# PDU_v3_1.net
KiCad netlist of a schematic drawn in EAGLE
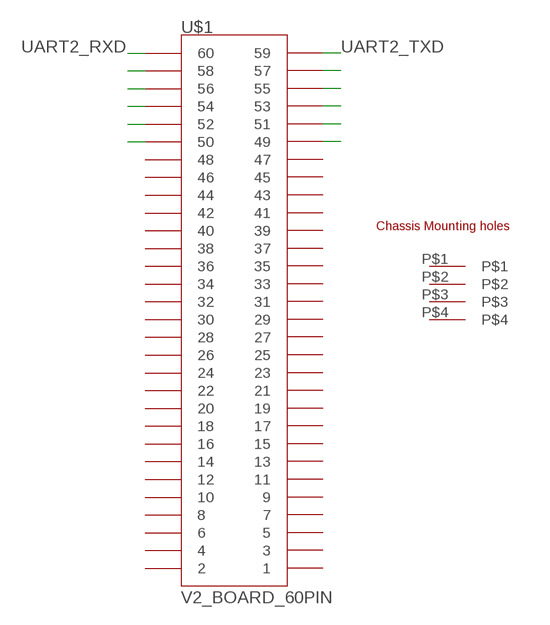
[diagram p0: schematic, sheet 1]
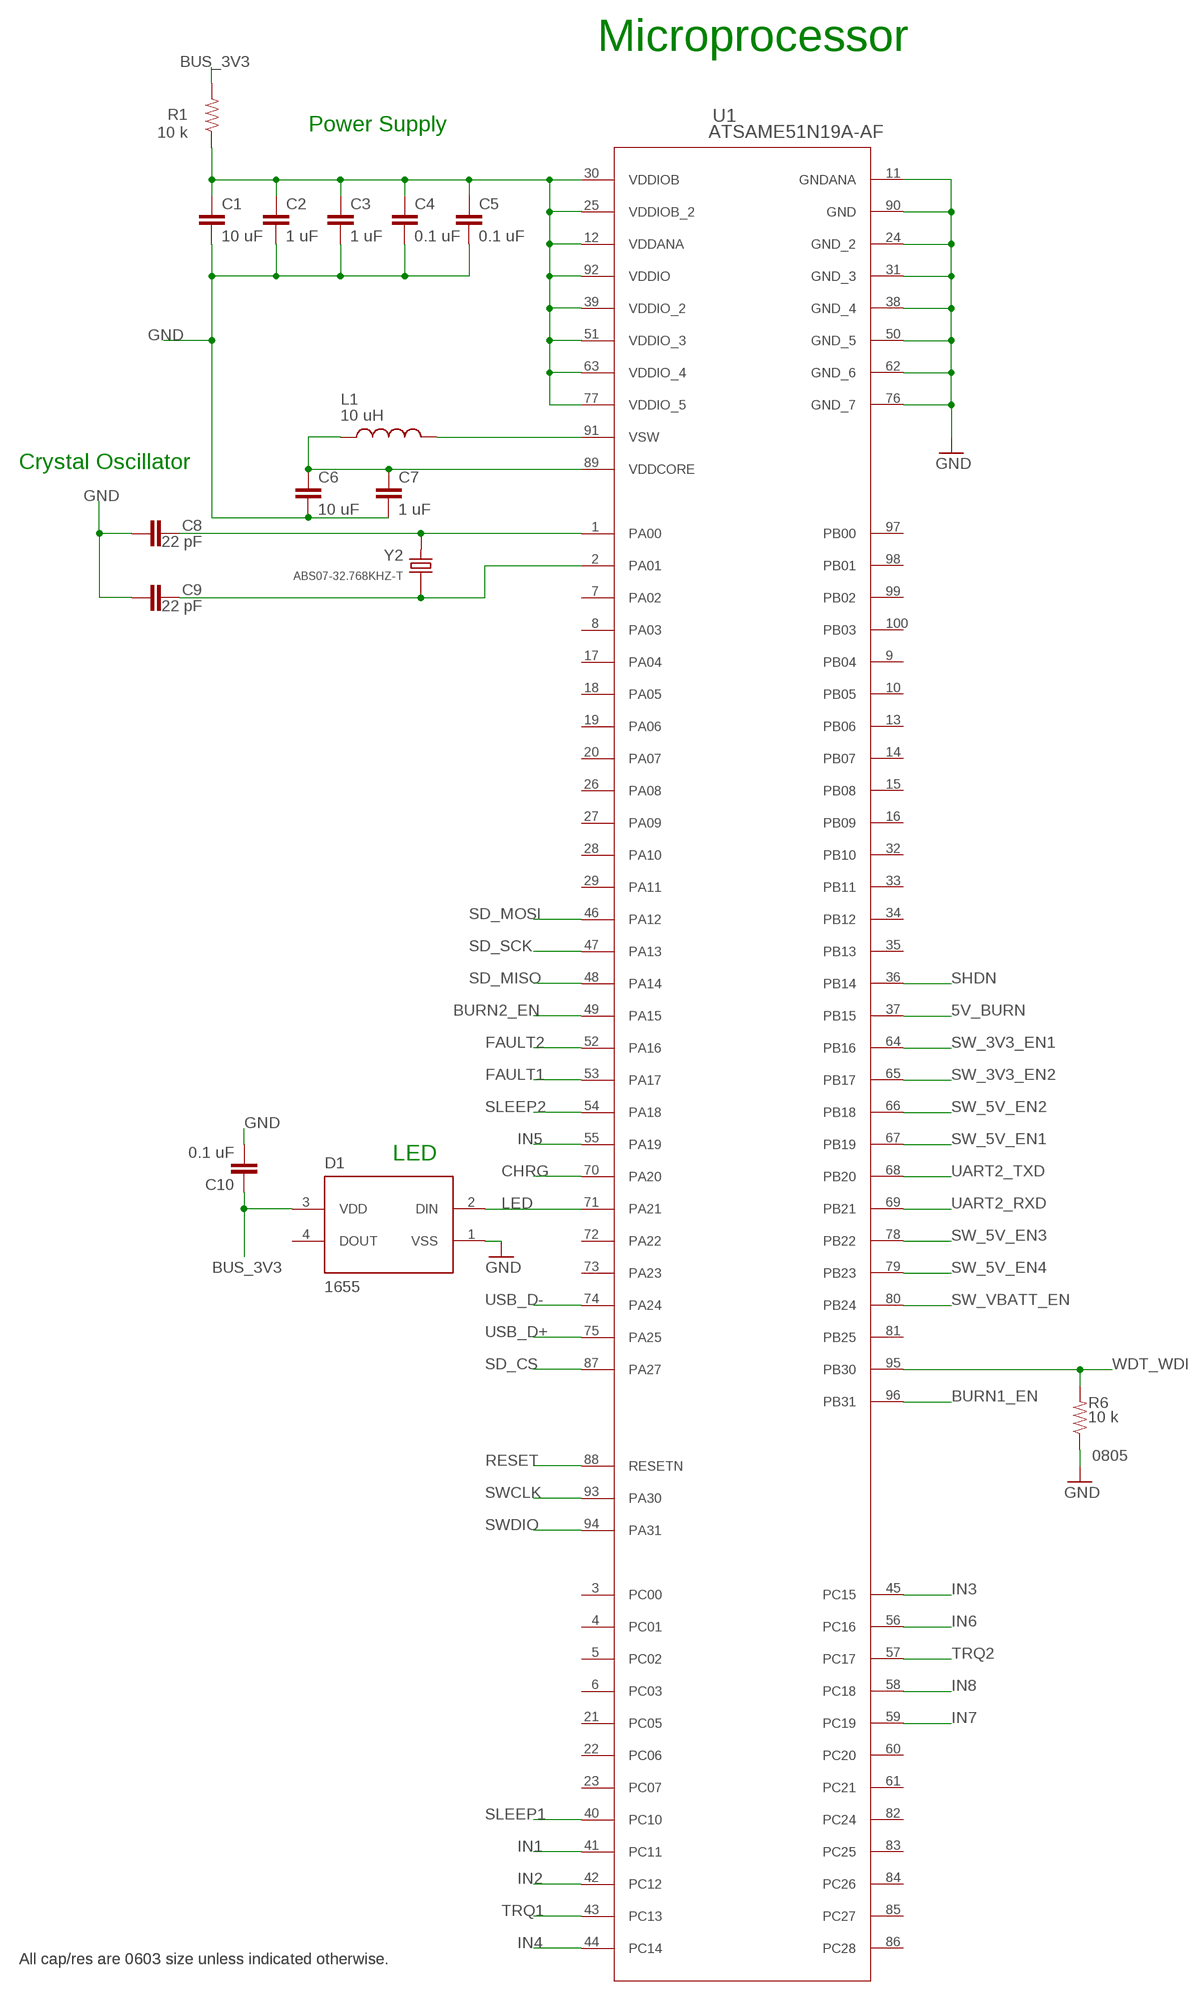
[diagram p1: schematic, sheet 2]
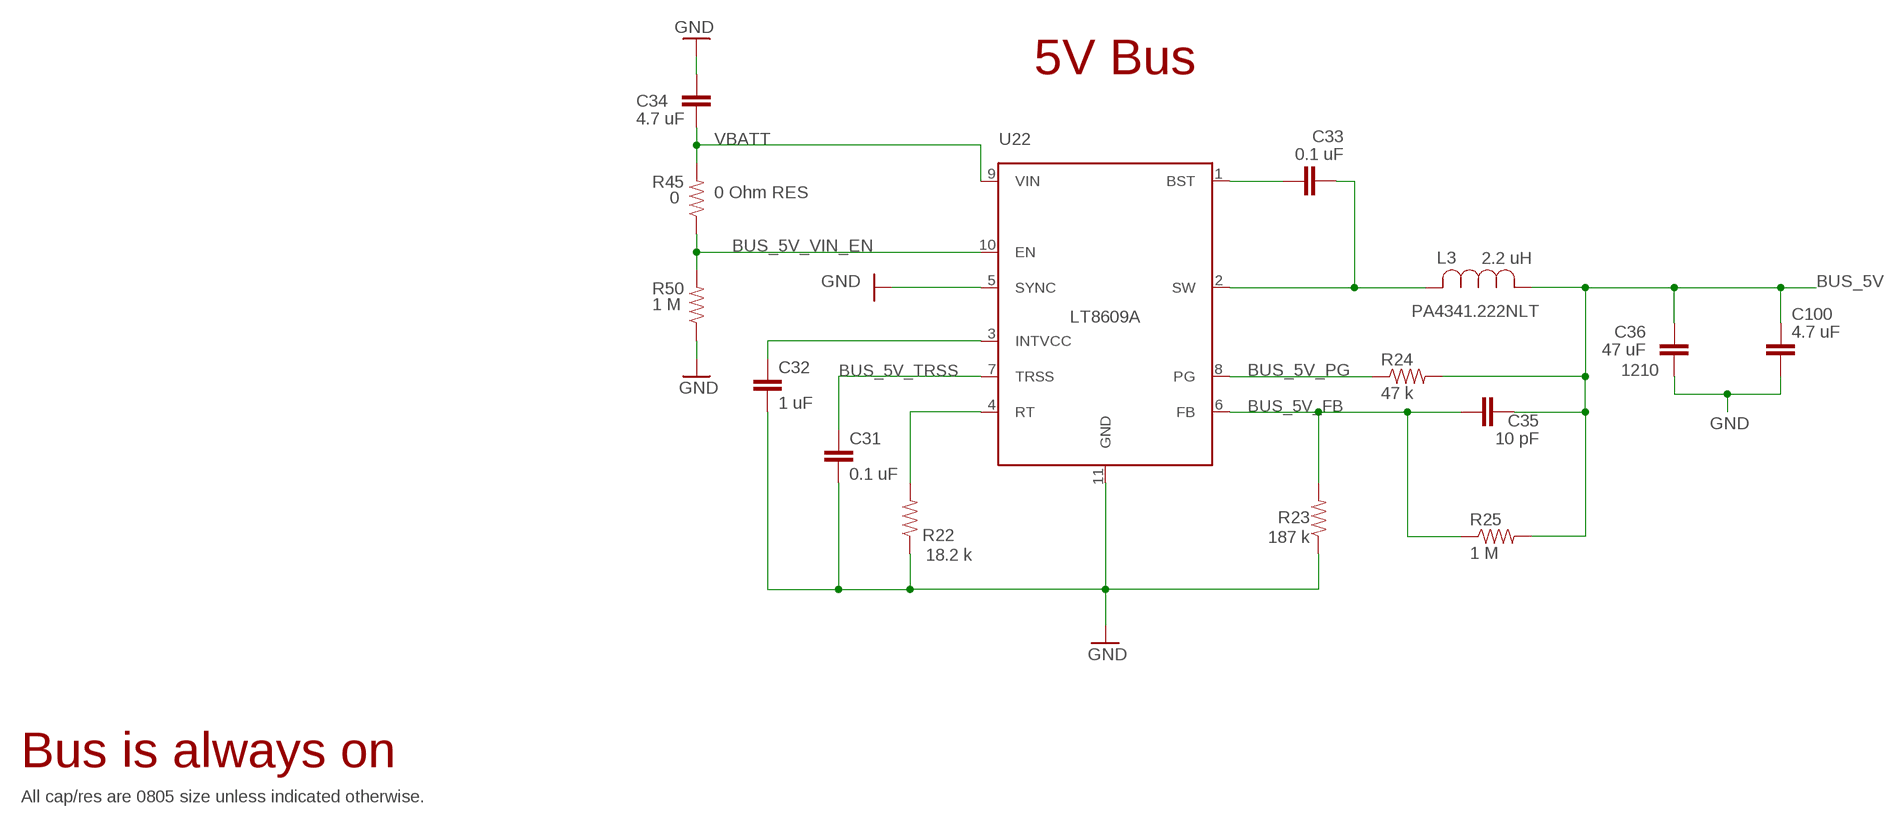
[diagram p2: schematic, sheet 3]

(export (version "E")
  (design (tool "Eeschema 10.0.6"))
  (components
    (comp (ref "C31")
      (value "0.1 uF")
      (footprint "eagle-import:0805")
      (libsource (lib "eagle-import") (part "CAP0805"))
    )
    (comp (ref "C32")
      (value "1 uF")
      (footprint "eagle-import:0805")
      (libsource (lib "eagle-import") (part "CAP0805"))
    )
    (comp (ref "C33")
      (value "0.1 uF")
      (footprint "eagle-import:0805")
      (libsource (lib "eagle-import") (part "CAP0805"))
    )
    (comp (ref "C34")
      (value "4.7 uF")
      (footprint "eagle-import:0805")
      (libsource (lib "eagle-import") (part "CAP0805"))
    )
    (comp (ref "C35")
      (value "10 pF")
      (footprint "eagle-import:0805")
      (libsource (lib "eagle-import") (part "CAP0805"))
    )
    (comp (ref "C36")
      (value "47 uF")
      (footprint "eagle-import:1210")
      (libsource (lib "eagle-import") (part "CAP1210"))
    )
    (comp (ref "C100")
      (value "4.7 uF")
      (footprint "eagle-import:0805")
      (libsource (lib "eagle-import") (part "CAP0805"))
    )
    (comp (ref "L3")
      (value "PA4341.222NLT")
      (footprint "eagle-import:IND_222NLT_PUL")
      (fields (field (name "COPYRIGHT") "Copyright (C) 2021 Ultra Librarian. All rights reserved."))
      (libsource (lib "eagle-import") (part "PA4341.222NLT"))
    )
    (comp (ref "R22")
      (value "18.2 k")
      (footprint "eagle-import:0805")
      (libsource (lib "eagle-import") (part "RESISTOR0805-RES"))
    )
    (comp (ref "R23")
      (value "187 k")
      (footprint "eagle-import:0805")
      (libsource (lib "eagle-import") (part "RESISTOR0805-RES"))
    )
    (comp (ref "R24")
      (value "47 k")
      (footprint "eagle-import:0805")
      (libsource (lib "eagle-import") (part "RESISTOR0805-RES"))
    )
    (comp (ref "R25")
      (value "1 M")
      (footprint "eagle-import:0805")
      (libsource (lib "eagle-import") (part "RESISTOR0805-RES"))
    )
    (comp (ref "R45")
      (value "0")
      (footprint "eagle-import:0805")
      (libsource (lib "eagle-import") (part "RESISTOR0805-RES"))
    )
    (comp (ref "R50")
      (value "1 M")
      (footprint "eagle-import:0805")
      (libsource (lib "eagle-import") (part "RESISTOR0805-RES"))
    )
    (comp (ref "U22")
      (value "LT8609A")
      (footprint "eagle-import:MSOP-10_MSE")
      (libsource (lib "eagle-import") (part "LT8609A"))
    )
    (comp (ref "C1")
      (value "10 uF")
      (footprint "eagle-import:0603-CAP")
      (libsource (lib "eagle-import") (part "CAP0603-CAP"))
    )
    (comp (ref "C2")
      (value "1 uF")
      (footprint "eagle-import:0603-CAP")
      (libsource (lib "eagle-import") (part "CAP0603-CAP"))
    )
    (comp (ref "C3")
      (value "1 uF")
      (footprint "eagle-import:0603-CAP")
      (libsource (lib "eagle-import") (part "CAP0603-CAP"))
    )
    (comp (ref "C4")
      (value "0.1 uF")
      (footprint "eagle-import:0603-CAP")
      (libsource (lib "eagle-import") (part "CAP0603-CAP"))
    )
    (comp (ref "C5")
      (value "0.1 uF")
      (footprint "eagle-import:0603-CAP")
      (libsource (lib "eagle-import") (part "CAP0603-CAP"))
    )
    (comp (ref "C6")
      (value "10 uF")
      (footprint "eagle-import:0603-CAP")
      (libsource (lib "eagle-import") (part "CAP0603-CAP"))
    )
    (comp (ref "C7")
      (value "1 uF")
      (footprint "eagle-import:0603-CAP")
      (libsource (lib "eagle-import") (part "CAP0603-CAP"))
    )
    (comp (ref "C8")
      (value "22 pF")
      (footprint "eagle-import:0603-CAP")
      (libsource (lib "eagle-import") (part "CAP0603-CAP"))
    )
    (comp (ref "C9")
      (value "22 pF")
      (footprint "eagle-import:0603-CAP")
      (libsource (lib "eagle-import") (part "CAP0603-CAP"))
    )
    (comp (ref "C10")
      (value "0.1 uF")
      (footprint "eagle-import:0603-CAP")
      (libsource (lib "eagle-import") (part "CAP0603-CAP"))
    )
    (comp (ref "D1")
      (value "1655")
      (footprint "eagle-import:LED_1655")
      (fields (field (name "MF") "Adafruit"))
      (libsource (lib "eagle-import") (part "1655"))
    )
    (comp (ref "L1")
      (value "10 uH")
      (footprint "eagle-import:INDC2012X100N")
      (fields
        (field (name "DIGI-KEY_PART_NUMBER") "587-1632-1-ND")
        (field (name "MF") "Taiyo Yuden")
        (field (name "MP") "CBL2012T100M")
      )
      (libsource (lib "eagle-import") (part "CBL2012T100M"))
    )
    (comp (ref "R1")
      (value "10 k")
      (footprint "eagle-import:0603-RES")
      (libsource (lib "eagle-import") (part "RESISTOR0603-RES"))
    )
    (comp (ref "R6")
      (value "10 k")
      (footprint "eagle-import:0805")
      (libsource (lib "eagle-import") (part "RESISTOR0805-RES"))
    )
    (comp (ref "U1")
      (value "ATSAME51N19A-AF")
      (footprint "eagle-import:TQFP100_14X14MC_MCH")
      (fields (field (name "COPYRIGHT") "Copyright (C) 2018 Accelerated Designs. All rights reserved"))
      (libsource (lib "eagle-import") (part "ATSAME51N19A-AF"))
    )
    (comp (ref "Y2")
      (value "ABS07-32.768KHZ-T")
      (footprint "eagle-import:XTAL_ABS07-32.768KHZ-T")
      (fields (field (name "DIGI-KEY_PART_NUMBER") "535-9542-1-ND") (field (name "MF") "Abracon"))
      (libsource (lib "eagle-import") (part "ABS07-32.768KHZ-T"))
    )
    (comp (ref "U$1")
      (value "V2_BOARD_60PIN")
      (footprint "eagle-import:PC104_WCONN_BACKPLANE_HEADER")
      (libsource (lib "eagle-import") (part "V2_BOARD_60PIN"))
    )
  )
  (nets
    (net (code "1") (name "5V_BURN") (class "Default")
      (node (ref "U1") (pin "37") (pinfunction "PB15_37") (pintype "bidirectional"))
    )
    (net (code "2") (name "BURN1_EN") (class "Default")
      (node (ref "U1") (pin "96") (pinfunction "PB31_96") (pintype "bidirectional"))
    )
    (net (code "3") (name "BURN2_EN") (class "Default")
      (node (ref "U1") (pin "49") (pinfunction "PA15_49") (pintype "bidirectional"))
    )
    (net (code "4") (name "BUS_3V3") (class "Default")
      (node (ref "C10") (pin "1") (pinfunction "1_1") (pintype "passive"))
      (node (ref "D1") (pin "3") (pinfunction "VDD_3") (pintype "power_in"))
      (node (ref "R1") (pin "2") (pinfunction "2_2") (pintype "passive"))
    )
    (net (code "5") (name "BUS_5V") (class "Default")
      (node (ref "C100") (pin "1") (pinfunction "1_1") (pintype "passive"))
      (node (ref "C35") (pin "2") (pinfunction "2_2") (pintype "passive"))
      (node (ref "C36") (pin "1") (pinfunction "1_1") (pintype "passive"))
      (node (ref "L3") (pin "1") (pinfunction "1_1") (pintype "passive"))
      (node (ref "R24") (pin "2") (pinfunction "2_2") (pintype "passive"))
      (node (ref "R25") (pin "2") (pinfunction "2_2") (pintype "passive"))
    )
    (net (code "6") (name "BUS_5V_FB") (class "Default")
      (node (ref "C35") (pin "1") (pinfunction "1_1") (pintype "passive"))
      (node (ref "R23") (pin "2") (pinfunction "2_2") (pintype "passive"))
      (node (ref "R25") (pin "1") (pinfunction "1_1") (pintype "passive"))
      (node (ref "U22") (pin "6") (pinfunction "FB_6") (pintype "bidirectional"))
    )
    (net (code "7") (name "BUS_5V_PG") (class "Default")
      (node (ref "R24") (pin "1") (pinfunction "1_1") (pintype "passive"))
      (node (ref "U22") (pin "8") (pinfunction "PG_8") (pintype "bidirectional"))
    )
    (net (code "8") (name "BUS_5V_TRSS") (class "Default")
      (node (ref "C31") (pin "1") (pinfunction "1_1") (pintype "passive"))
      (node (ref "U22") (pin "7") (pinfunction "TRSS_7") (pintype "bidirectional"))
    )
    (net (code "9") (name "BUS_5V_VIN_EN") (class "Default")
      (node (ref "R45") (pin "1") (pinfunction "1_1") (pintype "passive"))
      (node (ref "R50") (pin "2") (pinfunction "2_2") (pintype "passive"))
      (node (ref "U22") (pin "10") (pinfunction "EN_10") (pintype "bidirectional"))
    )
    (net (code "10") (name "CHRG") (class "Default")
      (node (ref "U1") (pin "70") (pinfunction "PA20_70") (pintype "bidirectional"))
    )
    (net (code "11") (name "FAULT1") (class "Default")
      (node (ref "U1") (pin "53") (pinfunction "PA17_53") (pintype "bidirectional"))
    )
    (net (code "12") (name "FAULT2") (class "Default")
      (node (ref "U1") (pin "52") (pinfunction "PA16_52") (pintype "bidirectional"))
    )
    (net (code "13") (name "GND") (class "Default")
      (node (ref "C1") (pin "2") (pinfunction "2_2") (pintype "passive"))
      (node (ref "C10") (pin "2") (pinfunction "2_2") (pintype "passive"))
      (node (ref "C100") (pin "2") (pinfunction "2_2") (pintype "passive"))
      (node (ref "C2") (pin "2") (pinfunction "2_2") (pintype "passive"))
      (node (ref "C3") (pin "2") (pinfunction "2_2") (pintype "passive"))
      (node (ref "C31") (pin "2") (pinfunction "2_2") (pintype "passive"))
      (node (ref "C32") (pin "2") (pinfunction "2_2") (pintype "passive"))
      (node (ref "C34") (pin "2") (pinfunction "2_2") (pintype "passive"))
      (node (ref "C36") (pin "2") (pinfunction "2_2") (pintype "passive"))
      (node (ref "C4") (pin "2") (pinfunction "2_2") (pintype "passive"))
      (node (ref "C5") (pin "2") (pinfunction "2_2") (pintype "passive"))
      (node (ref "C6") (pin "2") (pinfunction "2_2") (pintype "passive"))
      (node (ref "C7") (pin "2") (pinfunction "2_2") (pintype "passive"))
      (node (ref "C8") (pin "1") (pinfunction "1_1") (pintype "passive"))
      (node (ref "C9") (pin "1") (pinfunction "1_1") (pintype "passive"))
      (node (ref "D1") (pin "1") (pinfunction "VSS_1") (pintype "power_in"))
      (node (ref "R22") (pin "1") (pinfunction "1_1") (pintype "passive"))
      (node (ref "R23") (pin "1") (pinfunction "1_1") (pintype "passive"))
      (node (ref "R50") (pin "1") (pinfunction "1_1") (pintype "passive"))
      (node (ref "R6") (pin "1") (pinfunction "1_1") (pintype "passive"))
      (node (ref "U1") (pin "11") (pinfunction "GNDANA_11") (pintype "passive"))
      (node (ref "U1") (pin "24") (pinfunction "GND_2_24") (pintype "passive"))
      (node (ref "U1") (pin "31") (pinfunction "GND_3_31") (pintype "passive"))
      (node (ref "U1") (pin "38") (pinfunction "GND_4_38") (pintype "passive"))
      (node (ref "U1") (pin "50") (pinfunction "GND_5_50") (pintype "passive"))
      (node (ref "U1") (pin "62") (pinfunction "GND_6_62") (pintype "passive"))
      (node (ref "U1") (pin "76") (pinfunction "GND_7_76") (pintype "passive"))
      (node (ref "U1") (pin "90") (pinfunction "GND_90") (pintype "passive"))
      (node (ref "U22") (pin "11") (pinfunction "GND_11") (pintype "bidirectional"))
      (node (ref "U22") (pin "5") (pinfunction "SYNC_5") (pintype "bidirectional"))
    )
    (net (code "14") (name "IN1") (class "Default")
      (node (ref "U1") (pin "41") (pinfunction "PC11_41") (pintype "bidirectional"))
    )
    (net (code "15") (name "IN2") (class "Default")
      (node (ref "U1") (pin "42") (pinfunction "PC12_42") (pintype "bidirectional"))
    )
    (net (code "16") (name "IN3") (class "Default")
      (node (ref "U1") (pin "45") (pinfunction "PC15_45") (pintype "bidirectional"))
    )
    (net (code "17") (name "IN4") (class "Default")
      (node (ref "U1") (pin "44") (pinfunction "PC14_44") (pintype "bidirectional"))
    )
    (net (code "18") (name "IN5") (class "Default")
      (node (ref "U1") (pin "55") (pinfunction "PA19_55") (pintype "bidirectional"))
    )
    (net (code "19") (name "IN6") (class "Default")
      (node (ref "U1") (pin "56") (pinfunction "PC16_56") (pintype "bidirectional"))
    )
    (net (code "20") (name "IN7") (class "Default")
      (node (ref "U1") (pin "59") (pinfunction "PC19_59") (pintype "bidirectional"))
    )
    (net (code "21") (name "IN8") (class "Default")
      (node (ref "U1") (pin "58") (pinfunction "PC18_58") (pintype "bidirectional"))
    )
    (net (code "22") (name "LED") (class "Default")
      (node (ref "D1") (pin "2") (pinfunction "DIN_2") (pintype "input"))
      (node (ref "U1") (pin "71") (pinfunction "PA21_71") (pintype "bidirectional"))
    )
    (net (code "23") (name "Net-(U1-PA00)") (class "Default")
      (node (ref "C8") (pin "2") (pinfunction "2_2") (pintype "passive"))
      (node (ref "U1") (pin "1") (pinfunction "PA00_1") (pintype "bidirectional"))
      (node (ref "Y2") (pin "2") (pinfunction "2_2") (pintype "passive"))
    )
    (net (code "24") (name "Net-(U1-PA01)") (class "Default")
      (node (ref "C9") (pin "2") (pinfunction "2_2") (pintype "passive"))
      (node (ref "U1") (pin "2") (pinfunction "PA01_2") (pintype "bidirectional"))
      (node (ref "Y2") (pin "1") (pinfunction "1_1") (pintype "passive"))
    )
    (net (code "25") (name "Net-(U1-VDDANA)") (class "Default")
      (node (ref "C1") (pin "1") (pinfunction "1_1") (pintype "passive"))
      (node (ref "C2") (pin "1") (pinfunction "1_1") (pintype "passive"))
      (node (ref "C3") (pin "1") (pinfunction "1_1") (pintype "passive"))
      (node (ref "C4") (pin "1") (pinfunction "1_1") (pintype "passive"))
      (node (ref "C5") (pin "1") (pinfunction "1_1") (pintype "passive"))
      (node (ref "R1") (pin "1") (pinfunction "1_1") (pintype "passive"))
      (node (ref "U1") (pin "12") (pinfunction "VDDANA_12") (pintype "power_in"))
      (node (ref "U1") (pin "25") (pinfunction "VDDIOB_2_25") (pintype "power_in"))
      (node (ref "U1") (pin "30") (pinfunction "VDDIOB_30") (pintype "power_in"))
      (node (ref "U1") (pin "39") (pinfunction "VDDIO_2_39") (pintype "power_in"))
      (node (ref "U1") (pin "51") (pinfunction "VDDIO_3_51") (pintype "power_in"))
      (node (ref "U1") (pin "63") (pinfunction "VDDIO_4_63") (pintype "power_in"))
      (node (ref "U1") (pin "77") (pinfunction "VDDIO_5_77") (pintype "power_in"))
      (node (ref "U1") (pin "92") (pinfunction "VDDIO_92") (pintype "power_in"))
    )
    (net (code "26") (name "Net-(U1-VDDCORE)") (class "Default")
      (node (ref "C6") (pin "1") (pinfunction "1_1") (pintype "passive"))
      (node (ref "C7") (pin "1") (pinfunction "1_1") (pintype "passive"))
      (node (ref "L1") (pin "1") (pinfunction "1_1") (pintype "passive"))
      (node (ref "U1") (pin "89") (pinfunction "VDDCORE_89") (pintype "power_in"))
    )
    (net (code "27") (name "Net-(U1-VSW)") (class "Default")
      (node (ref "L1") (pin "2") (pinfunction "2_2") (pintype "passive"))
      (node (ref "U1") (pin "91") (pinfunction "VSW_91") (pintype "passive"))
    )
    (net (code "28") (name "Net-(U22-BST)") (class "Default")
      (node (ref "C33") (pin "1") (pinfunction "1_1") (pintype "passive"))
      (node (ref "U22") (pin "1") (pinfunction "BST_1") (pintype "bidirectional"))
    )
    (net (code "29") (name "Net-(U22-INTVCC)") (class "Default")
      (node (ref "C32") (pin "1") (pinfunction "1_1") (pintype "passive"))
      (node (ref "U22") (pin "3") (pinfunction "INTVCC_3") (pintype "bidirectional"))
    )
    (net (code "30") (name "Net-(U22-RT)") (class "Default")
      (node (ref "R22") (pin "2") (pinfunction "2_2") (pintype "passive"))
      (node (ref "U22") (pin "4") (pinfunction "RT_4") (pintype "bidirectional"))
    )
    (net (code "31") (name "Net-(U22-SW)") (class "Default")
      (node (ref "C33") (pin "2") (pinfunction "2_2") (pintype "passive"))
      (node (ref "L3") (pin "2") (pinfunction "2_2") (pintype "passive"))
      (node (ref "U22") (pin "2") (pinfunction "SW_2") (pintype "bidirectional"))
    )
    (net (code "32") (name "RESET") (class "Default")
      (node (ref "U1") (pin "88") (pinfunction "RESETN_88") (pintype "passive"))
    )
    (net (code "33") (name "SD_CS") (class "Default")
      (node (ref "U1") (pin "87") (pinfunction "PA27_87") (pintype "bidirectional"))
    )
    (net (code "34") (name "SD_MISO") (class "Default")
      (node (ref "U1") (pin "48") (pinfunction "PA14_48") (pintype "bidirectional"))
    )
    (net (code "35") (name "SD_MOSI") (class "Default")
      (node (ref "U1") (pin "46") (pinfunction "PA12_46") (pintype "bidirectional"))
    )
    (net (code "36") (name "SD_SCK") (class "Default")
      (node (ref "U1") (pin "47") (pinfunction "PA13_47") (pintype "bidirectional"))
    )
    (net (code "37") (name "SHDN") (class "Default")
      (node (ref "U1") (pin "36") (pinfunction "PB14_36") (pintype "bidirectional"))
    )
    (net (code "38") (name "SLEEP1") (class "Default")
      (node (ref "U1") (pin "40") (pinfunction "PC10_40") (pintype "bidirectional"))
    )
    (net (code "39") (name "SLEEP2") (class "Default")
      (node (ref "U1") (pin "54") (pinfunction "PA18_54") (pintype "bidirectional"))
    )
    (net (code "40") (name "SWCLK") (class "Default")
      (node (ref "U1") (pin "93") (pinfunction "PA30_93") (pintype "bidirectional"))
    )
    (net (code "41") (name "SWDIO") (class "Default")
      (node (ref "U1") (pin "94") (pinfunction "PA31_94") (pintype "bidirectional"))
    )
    (net (code "42") (name "SW_3V3_EN1") (class "Default")
      (node (ref "U1") (pin "64") (pinfunction "PB16_64") (pintype "bidirectional"))
    )
    (net (code "43") (name "SW_3V3_EN2") (class "Default")
      (node (ref "U1") (pin "65") (pinfunction "PB17_65") (pintype "bidirectional"))
    )
    (net (code "44") (name "SW_5V_EN1") (class "Default")
      (node (ref "U1") (pin "67") (pinfunction "PB19_67") (pintype "bidirectional"))
    )
    (net (code "45") (name "SW_5V_EN2") (class "Default")
      (node (ref "U1") (pin "66") (pinfunction "PB18_66") (pintype "bidirectional"))
    )
    (net (code "46") (name "SW_5V_EN3") (class "Default")
      (node (ref "U1") (pin "78") (pinfunction "PB22_78") (pintype "bidirectional"))
    )
    (net (code "47") (name "SW_5V_EN4") (class "Default")
      (node (ref "U1") (pin "79") (pinfunction "PB23_79") (pintype "bidirectional"))
    )
    (net (code "48") (name "SW_VBATT_EN") (class "Default")
      (node (ref "U1") (pin "80") (pinfunction "PB24_80") (pintype "bidirectional"))
    )
    (net (code "49") (name "TRQ1") (class "Default")
      (node (ref "U1") (pin "43") (pinfunction "PC13_43") (pintype "bidirectional"))
    )
    (net (code "50") (name "TRQ2") (class "Default")
      (node (ref "U1") (pin "57") (pinfunction "PC17_57") (pintype "bidirectional"))
    )
    (net (code "51") (name "UART2_RXD") (class "Default")
      (node (ref "U$1") (pin "60") (pinfunction "60_60") (pintype "bidirectional"))
      (node (ref "U1") (pin "69") (pinfunction "PB21_69") (pintype "bidirectional"))
    )
    (net (code "52") (name "UART2_TXD") (class "Default")
      (node (ref "U$1") (pin "59") (pinfunction "59_59") (pintype "bidirectional"))
      (node (ref "U1") (pin "68") (pinfunction "PB20_68") (pintype "bidirectional"))
    )
    (net (code "53") (name "USB_D+") (class "Default")
      (node (ref "U1") (pin "75") (pinfunction "PA25_75") (pintype "bidirectional"))
    )
    (net (code "54") (name "USB_D-") (class "Default")
      (node (ref "U1") (pin "74") (pinfunction "PA24_74") (pintype "bidirectional"))
    )
    (net (code "55") (name "VBATT") (class "Default")
      (node (ref "C34") (pin "1") (pinfunction "1_1") (pintype "passive"))
      (node (ref "R45") (pin "2") (pinfunction "2_2") (pintype "passive"))
      (node (ref "U22") (pin "9") (pinfunction "VIN_9") (pintype "bidirectional"))
    )
    (net (code "56") (name "WDT_WDI") (class "Default")
      (node (ref "R6") (pin "2") (pinfunction "2_2") (pintype "passive"))
      (node (ref "U1") (pin "95") (pinfunction "PB30_95") (pintype "bidirectional"))
    )
    (net (code "57") (name "unconnected-(D1-DOUT-Pad4)") (class "Default")
      (node (ref "D1") (pin "4") (pinfunction "DOUT_4") (pintype "output"))
    )
    (net (code "58") (name "unconnected-(U$1-Pad1)") (class "Default")
      (node (ref "U$1") (pin "1") (pinfunction "1_1") (pintype "bidirectional"))
    )
    (net (code "59") (name "unconnected-(U$1-Pad2)") (class "Default")
      (node (ref "U$1") (pin "2") (pinfunction "2_2") (pintype "bidirectional"))
    )
    (net (code "60") (name "unconnected-(U$1-Pad3)") (class "Default")
      (node (ref "U$1") (pin "3") (pinfunction "3_3") (pintype "bidirectional"))
    )
    (net (code "61") (name "unconnected-(U$1-Pad4)") (class "Default")
      (node (ref "U$1") (pin "4") (pinfunction "4_4") (pintype "bidirectional"))
    )
    (net (code "62") (name "unconnected-(U$1-Pad5)") (class "Default")
      (node (ref "U$1") (pin "5") (pinfunction "5_5") (pintype "bidirectional"))
    )
    (net (code "63") (name "unconnected-(U$1-Pad6)") (class "Default")
      (node (ref "U$1") (pin "6") (pinfunction "6_6") (pintype "bidirectional"))
    )
    (net (code "64") (name "unconnected-(U$1-Pad7)") (class "Default")
      (node (ref "U$1") (pin "7") (pinfunction "7_7") (pintype "bidirectional"))
    )
    (net (code "65") (name "unconnected-(U$1-Pad8)") (class "Default")
      (node (ref "U$1") (pin "8") (pinfunction "8_8") (pintype "bidirectional"))
    )
    (net (code "66") (name "unconnected-(U$1-Pad9)") (class "Default")
      (node (ref "U$1") (pin "9") (pinfunction "9_9") (pintype "bidirectional"))
    )
    (net (code "67") (name "unconnected-(U$1-Pad10)") (class "Default")
      (node (ref "U$1") (pin "10") (pinfunction "10_10") (pintype "bidirectional"))
    )
    (net (code "68") (name "unconnected-(U$1-Pad11)") (class "Default")
      (node (ref "U$1") (pin "11") (pinfunction "11_11") (pintype "bidirectional"))
    )
    (net (code "69") (name "unconnected-(U$1-Pad12)") (class "Default")
      (node (ref "U$1") (pin "12") (pinfunction "12_12") (pintype "bidirectional"))
    )
    (net (code "70") (name "unconnected-(U$1-Pad13)") (class "Default")
      (node (ref "U$1") (pin "13") (pinfunction "13_13") (pintype "bidirectional"))
    )
    (net (code "71") (name "unconnected-(U$1-Pad14)") (class "Default")
      (node (ref "U$1") (pin "14") (pinfunction "14_14") (pintype "bidirectional"))
    )
    (net (code "72") (name "unconnected-(U$1-Pad15)") (class "Default")
      (node (ref "U$1") (pin "15") (pinfunction "15_15") (pintype "bidirectional"))
    )
    (net (code "73") (name "unconnected-(U$1-Pad16)") (class "Default")
      (node (ref "U$1") (pin "16") (pinfunction "16_16") (pintype "bidirectional"))
    )
    (net (code "74") (name "unconnected-(U$1-Pad17)") (class "Default")
      (node (ref "U$1") (pin "17") (pinfunction "17_17") (pintype "bidirectional"))
    )
    (net (code "75") (name "unconnected-(U$1-Pad18)") (class "Default")
      (node (ref "U$1") (pin "18") (pinfunction "18_18") (pintype "bidirectional"))
    )
    (net (code "76") (name "unconnected-(U$1-Pad19)") (class "Default")
      (node (ref "U$1") (pin "19") (pinfunction "19_19") (pintype "bidirectional"))
    )
    (net (code "77") (name "unconnected-(U$1-Pad20)") (class "Default")
      (node (ref "U$1") (pin "20") (pinfunction "20_20") (pintype "bidirectional"))
    )
    (net (code "78") (name "unconnected-(U$1-Pad21)") (class "Default")
      (node (ref "U$1") (pin "21") (pinfunction "21_21") (pintype "bidirectional"))
    )
    (net (code "79") (name "unconnected-(U$1-Pad22)") (class "Default")
      (node (ref "U$1") (pin "22") (pinfunction "22_22") (pintype "bidirectional"))
    )
    (net (code "80") (name "unconnected-(U$1-Pad23)") (class "Default")
      (node (ref "U$1") (pin "23") (pinfunction "23_23") (pintype "bidirectional"))
    )
    (net (code "81") (name "unconnected-(U$1-Pad24)") (class "Default")
      (node (ref "U$1") (pin "24") (pinfunction "24_24") (pintype "bidirectional"))
    )
    (net (code "82") (name "unconnected-(U$1-Pad25)") (class "Default")
      (node (ref "U$1") (pin "25") (pinfunction "25_25") (pintype "bidirectional"))
    )
    (net (code "83") (name "unconnected-(U$1-Pad26)") (class "Default")
      (node (ref "U$1") (pin "26") (pinfunction "26_26") (pintype "bidirectional"))
    )
    (net (code "84") (name "unconnected-(U$1-Pad27)") (class "Default")
      (node (ref "U$1") (pin "27") (pinfunction "27_27") (pintype "bidirectional"))
    )
    (net (code "85") (name "unconnected-(U$1-Pad28)") (class "Default")
      (node (ref "U$1") (pin "28") (pinfunction "28_28") (pintype "bidirectional"))
    )
    (net (code "86") (name "unconnected-(U$1-Pad29)") (class "Default")
      (node (ref "U$1") (pin "29") (pinfunction "29_29") (pintype "bidirectional"))
    )
    (net (code "87") (name "unconnected-(U$1-Pad30)") (class "Default")
      (node (ref "U$1") (pin "30") (pinfunction "30_30") (pintype "bidirectional"))
    )
    (net (code "88") (name "unconnected-(U$1-Pad31)") (class "Default")
      (node (ref "U$1") (pin "31") (pinfunction "31_31") (pintype "bidirectional"))
    )
    (net (code "89") (name "unconnected-(U$1-Pad32)") (class "Default")
      (node (ref "U$1") (pin "32") (pinfunction "32_32") (pintype "bidirectional"))
    )
    (net (code "90") (name "unconnected-(U$1-Pad33)") (class "Default")
      (node (ref "U$1") (pin "33") (pinfunction "33_33") (pintype "bidirectional"))
    )
    (net (code "91") (name "unconnected-(U$1-Pad34)") (class "Default")
      (node (ref "U$1") (pin "34") (pinfunction "34_34") (pintype "bidirectional"))
    )
    (net (code "92") (name "unconnected-(U$1-Pad35)") (class "Default")
      (node (ref "U$1") (pin "35") (pinfunction "35_35") (pintype "bidirectional"))
    )
    (net (code "93") (name "unconnected-(U$1-Pad36)") (class "Default")
      (node (ref "U$1") (pin "36") (pinfunction "36_36") (pintype "bidirectional"))
    )
    (net (code "94") (name "unconnected-(U$1-Pad37)") (class "Default")
      (node (ref "U$1") (pin "37") (pinfunction "37_37") (pintype "bidirectional"))
    )
    (net (code "95") (name "unconnected-(U$1-Pad38)") (class "Default")
      (node (ref "U$1") (pin "38") (pinfunction "38_38") (pintype "bidirectional"))
    )
    (net (code "96") (name "unconnected-(U$1-Pad39)") (class "Default")
      (node (ref "U$1") (pin "39") (pinfunction "39_39") (pintype "bidirectional"))
    )
    (net (code "97") (name "unconnected-(U$1-Pad40)") (class "Default")
      (node (ref "U$1") (pin "40") (pinfunction "40_40") (pintype "bidirectional"))
    )
    (net (code "98") (name "unconnected-(U$1-Pad41)") (class "Default")
      (node (ref "U$1") (pin "41") (pinfunction "41_41") (pintype "bidirectional"))
    )
    (net (code "99") (name "unconnected-(U$1-Pad42)") (class "Default")
      (node (ref "U$1") (pin "42") (pinfunction "42_42") (pintype "bidirectional"))
    )
    (net (code "100") (name "unconnected-(U$1-Pad43)") (class "Default")
      (node (ref "U$1") (pin "43") (pinfunction "43_43") (pintype "bidirectional"))
    )
    (net (code "101") (name "unconnected-(U$1-Pad44)") (class "Default")
      (node (ref "U$1") (pin "44") (pinfunction "44_44") (pintype "bidirectional"))
    )
    (net (code "102") (name "unconnected-(U$1-Pad45)") (class "Default")
      (node (ref "U$1") (pin "45") (pinfunction "45_45") (pintype "bidirectional"))
    )
    (net (code "103") (name "unconnected-(U$1-Pad46)") (class "Default")
      (node (ref "U$1") (pin "46") (pinfunction "46_46") (pintype "bidirectional"))
    )
    (net (code "104") (name "unconnected-(U$1-Pad47)") (class "Default")
      (node (ref "U$1") (pin "47") (pinfunction "47_47") (pintype "bidirectional"))
    )
    (net (code "105") (name "unconnected-(U$1-Pad48)") (class "Default")
      (node (ref "U$1") (pin "48") (pinfunction "48_48") (pintype "bidirectional"))
    )
    (net (code "106") (name "unconnected-(U$1-Pad49)") (class "Default")
      (node (ref "U$1") (pin "49") (pinfunction "49_49") (pintype "bidirectional"))
    )
    (net (code "107") (name "unconnected-(U$1-Pad50)") (class "Default")
      (node (ref "U$1") (pin "50") (pinfunction "50_50") (pintype "bidirectional"))
    )
    (net (code "108") (name "unconnected-(U$1-Pad51)") (class "Default")
      (node (ref "U$1") (pin "51") (pinfunction "51_51") (pintype "bidirectional"))
    )
    (net (code "109") (name "unconnected-(U$1-Pad52)") (class "Default")
      (node (ref "U$1") (pin "52") (pinfunction "52_52") (pintype "bidirectional"))
    )
    (net (code "110") (name "unconnected-(U$1-Pad53)") (class "Default")
      (node (ref "U$1") (pin "53") (pinfunction "53_53") (pintype "bidirectional"))
    )
    (net (code "111") (name "unconnected-(U$1-Pad54)") (class "Default")
      (node (ref "U$1") (pin "54") (pinfunction "54_54") (pintype "bidirectional"))
    )
    (net (code "112") (name "unconnected-(U$1-Pad55)") (class "Default")
      (node (ref "U$1") (pin "55") (pinfunction "55_55") (pintype "bidirectional"))
    )
    (net (code "113") (name "unconnected-(U$1-Pad56)") (class "Default")
      (node (ref "U$1") (pin "56") (pinfunction "56_56") (pintype "bidirectional"))
    )
    (net (code "114") (name "unconnected-(U$1-Pad57)") (class "Default")
      (node (ref "U$1") (pin "57") (pinfunction "57_57") (pintype "bidirectional"))
    )
    (net (code "115") (name "unconnected-(U$1-Pad58)") (class "Default")
      (node (ref "U$1") (pin "58") (pinfunction "58_58") (pintype "bidirectional"))
    )
    (net (code "116") (name "unconnected-(U$1-PadP$1)") (class "Default")
      (node (ref "U$1") (pin "P$1") (pinfunction "P$1_P$1") (pintype "bidirectional"))
    )
    (net (code "117") (name "unconnected-(U$1-PadP$2)") (class "Default")
      (node (ref "U$1") (pin "P$2") (pinfunction "P$2_P$2") (pintype "bidirectional"))
    )
    (net (code "118") (name "unconnected-(U$1-PadP$3)") (class "Default")
      (node (ref "U$1") (pin "P$3") (pinfunction "P$3_P$3") (pintype "bidirectional"))
    )
    (net (code "119") (name "unconnected-(U$1-PadP$4)") (class "Default")
      (node (ref "U$1") (pin "P$4") (pinfunction "P$4_P$4") (pintype "bidirectional"))
    )
    (net (code "120") (name "unconnected-(U1-PA02-Pad7)") (class "Default")
      (node (ref "U1") (pin "7") (pinfunction "PA02_7") (pintype "bidirectional"))
    )
    (net (code "121") (name "unconnected-(U1-PA03-Pad8)") (class "Default")
      (node (ref "U1") (pin "8") (pinfunction "PA03_8") (pintype "bidirectional"))
    )
    (net (code "122") (name "unconnected-(U1-PA04-Pad17)") (class "Default")
      (node (ref "U1") (pin "17") (pinfunction "PA04_17") (pintype "bidirectional"))
    )
    (net (code "123") (name "unconnected-(U1-PA05-Pad18)") (class "Default")
      (node (ref "U1") (pin "18") (pinfunction "PA05_18") (pintype "bidirectional"))
    )
    (net (code "124") (name "unconnected-(U1-PA06-Pad19)") (class "Default")
      (node (ref "U1") (pin "19") (pinfunction "PA06_19") (pintype "bidirectional"))
    )
    (net (code "125") (name "unconnected-(U1-PA07-Pad20)") (class "Default")
      (node (ref "U1") (pin "20") (pinfunction "PA07_20") (pintype "bidirectional"))
    )
    (net (code "126") (name "unconnected-(U1-PA08-Pad26)") (class "Default")
      (node (ref "U1") (pin "26") (pinfunction "PA08_26") (pintype "bidirectional"))
    )
    (net (code "127") (name "unconnected-(U1-PA09-Pad27)") (class "Default")
      (node (ref "U1") (pin "27") (pinfunction "PA09_27") (pintype "bidirectional"))
    )
    (net (code "128") (name "unconnected-(U1-PA10-Pad28)") (class "Default")
      (node (ref "U1") (pin "28") (pinfunction "PA10_28") (pintype "bidirectional"))
    )
    (net (code "129") (name "unconnected-(U1-PA11-Pad29)") (class "Default")
      (node (ref "U1") (pin "29") (pinfunction "PA11_29") (pintype "bidirectional"))
    )
    (net (code "130") (name "unconnected-(U1-PA22-Pad72)") (class "Default")
      (node (ref "U1") (pin "72") (pinfunction "PA22_72") (pintype "bidirectional"))
    )
    (net (code "131") (name "unconnected-(U1-PA23-Pad73)") (class "Default")
      (node (ref "U1") (pin "73") (pinfunction "PA23_73") (pintype "bidirectional"))
    )
    (net (code "132") (name "unconnected-(U1-PB00-Pad97)") (class "Default")
      (node (ref "U1") (pin "97") (pinfunction "PB00_97") (pintype "bidirectional"))
    )
    (net (code "133") (name "unconnected-(U1-PB01-Pad98)") (class "Default")
      (node (ref "U1") (pin "98") (pinfunction "PB01_98") (pintype "bidirectional"))
    )
    (net (code "134") (name "unconnected-(U1-PB02-Pad99)") (class "Default")
      (node (ref "U1") (pin "99") (pinfunction "PB02_99") (pintype "bidirectional"))
    )
    (net (code "135") (name "unconnected-(U1-PB03-Pad100)") (class "Default")
      (node (ref "U1") (pin "100") (pinfunction "PB03_100") (pintype "bidirectional"))
    )
    (net (code "136") (name "unconnected-(U1-PB04-Pad9)") (class "Default")
      (node (ref "U1") (pin "9") (pinfunction "PB04_9") (pintype "bidirectional"))
    )
    (net (code "137") (name "unconnected-(U1-PB05-Pad10)") (class "Default")
      (node (ref "U1") (pin "10") (pinfunction "PB05_10") (pintype "bidirectional"))
    )
    (net (code "138") (name "unconnected-(U1-PB06-Pad13)") (class "Default")
      (node (ref "U1") (pin "13") (pinfunction "PB06_13") (pintype "bidirectional"))
    )
    (net (code "139") (name "unconnected-(U1-PB07-Pad14)") (class "Default")
      (node (ref "U1") (pin "14") (pinfunction "PB07_14") (pintype "bidirectional"))
    )
    (net (code "140") (name "unconnected-(U1-PB08-Pad15)") (class "Default")
      (node (ref "U1") (pin "15") (pinfunction "PB08_15") (pintype "bidirectional"))
    )
    (net (code "141") (name "unconnected-(U1-PB09-Pad16)") (class "Default")
      (node (ref "U1") (pin "16") (pinfunction "PB09_16") (pintype "bidirectional"))
    )
    (net (code "142") (name "unconnected-(U1-PB10-Pad32)") (class "Default")
      (node (ref "U1") (pin "32") (pinfunction "PB10_32") (pintype "bidirectional"))
    )
    (net (code "143") (name "unconnected-(U1-PB11-Pad33)") (class "Default")
      (node (ref "U1") (pin "33") (pinfunction "PB11_33") (pintype "bidirectional"))
    )
    (net (code "144") (name "unconnected-(U1-PB12-Pad34)") (class "Default")
      (node (ref "U1") (pin "34") (pinfunction "PB12_34") (pintype "bidirectional"))
    )
    (net (code "145") (name "unconnected-(U1-PB13-Pad35)") (class "Default")
      (node (ref "U1") (pin "35") (pinfunction "PB13_35") (pintype "bidirectional"))
    )
    (net (code "146") (name "unconnected-(U1-PB25-Pad81)") (class "Default")
      (node (ref "U1") (pin "81") (pinfunction "PB25_81") (pintype "bidirectional"))
    )
    (net (code "147") (name "unconnected-(U1-PC00-Pad3)") (class "Default")
      (node (ref "U1") (pin "3") (pinfunction "PC00_3") (pintype "bidirectional"))
    )
    (net (code "148") (name "unconnected-(U1-PC01-Pad4)") (class "Default")
      (node (ref "U1") (pin "4") (pinfunction "PC01_4") (pintype "bidirectional"))
    )
    (net (code "149") (name "unconnected-(U1-PC02-Pad5)") (class "Default")
      (node (ref "U1") (pin "5") (pinfunction "PC02_5") (pintype "bidirectional"))
    )
    (net (code "150") (name "unconnected-(U1-PC03-Pad6)") (class "Default")
      (node (ref "U1") (pin "6") (pinfunction "PC03_6") (pintype "bidirectional"))
    )
    (net (code "151") (name "unconnected-(U1-PC05-Pad21)") (class "Default")
      (node (ref "U1") (pin "21") (pinfunction "PC05_21") (pintype "bidirectional"))
    )
    (net (code "152") (name "unconnected-(U1-PC06-Pad22)") (class "Default")
      (node (ref "U1") (pin "22") (pinfunction "PC06_22") (pintype "bidirectional"))
    )
    (net (code "153") (name "unconnected-(U1-PC07-Pad23)") (class "Default")
      (node (ref "U1") (pin "23") (pinfunction "PC07_23") (pintype "bidirectional"))
    )
    (net (code "154") (name "unconnected-(U1-PC20-Pad60)") (class "Default")
      (node (ref "U1") (pin "60") (pinfunction "PC20_60") (pintype "bidirectional"))
    )
    (net (code "155") (name "unconnected-(U1-PC21-Pad61)") (class "Default")
      (node (ref "U1") (pin "61") (pinfunction "PC21_61") (pintype "bidirectional"))
    )
    (net (code "156") (name "unconnected-(U1-PC24-Pad82)") (class "Default")
      (node (ref "U1") (pin "82") (pinfunction "PC24_82") (pintype "bidirectional"))
    )
    (net (code "157") (name "unconnected-(U1-PC25-Pad83)") (class "Default")
      (node (ref "U1") (pin "83") (pinfunction "PC25_83") (pintype "bidirectional"))
    )
    (net (code "158") (name "unconnected-(U1-PC26-Pad84)") (class "Default")
      (node (ref "U1") (pin "84") (pinfunction "PC26_84") (pintype "bidirectional"))
    )
    (net (code "159") (name "unconnected-(U1-PC27-Pad85)") (class "Default")
      (node (ref "U1") (pin "85") (pinfunction "PC27_85") (pintype "bidirectional"))
    )
    (net (code "160") (name "unconnected-(U1-PC28-Pad86)") (class "Default")
      (node (ref "U1") (pin "86") (pinfunction "PC28_86") (pintype "bidirectional"))
    )
  )
)
